# VCU_Schematic.net
KiCad netlist of a schematic drawn in Altium Designer
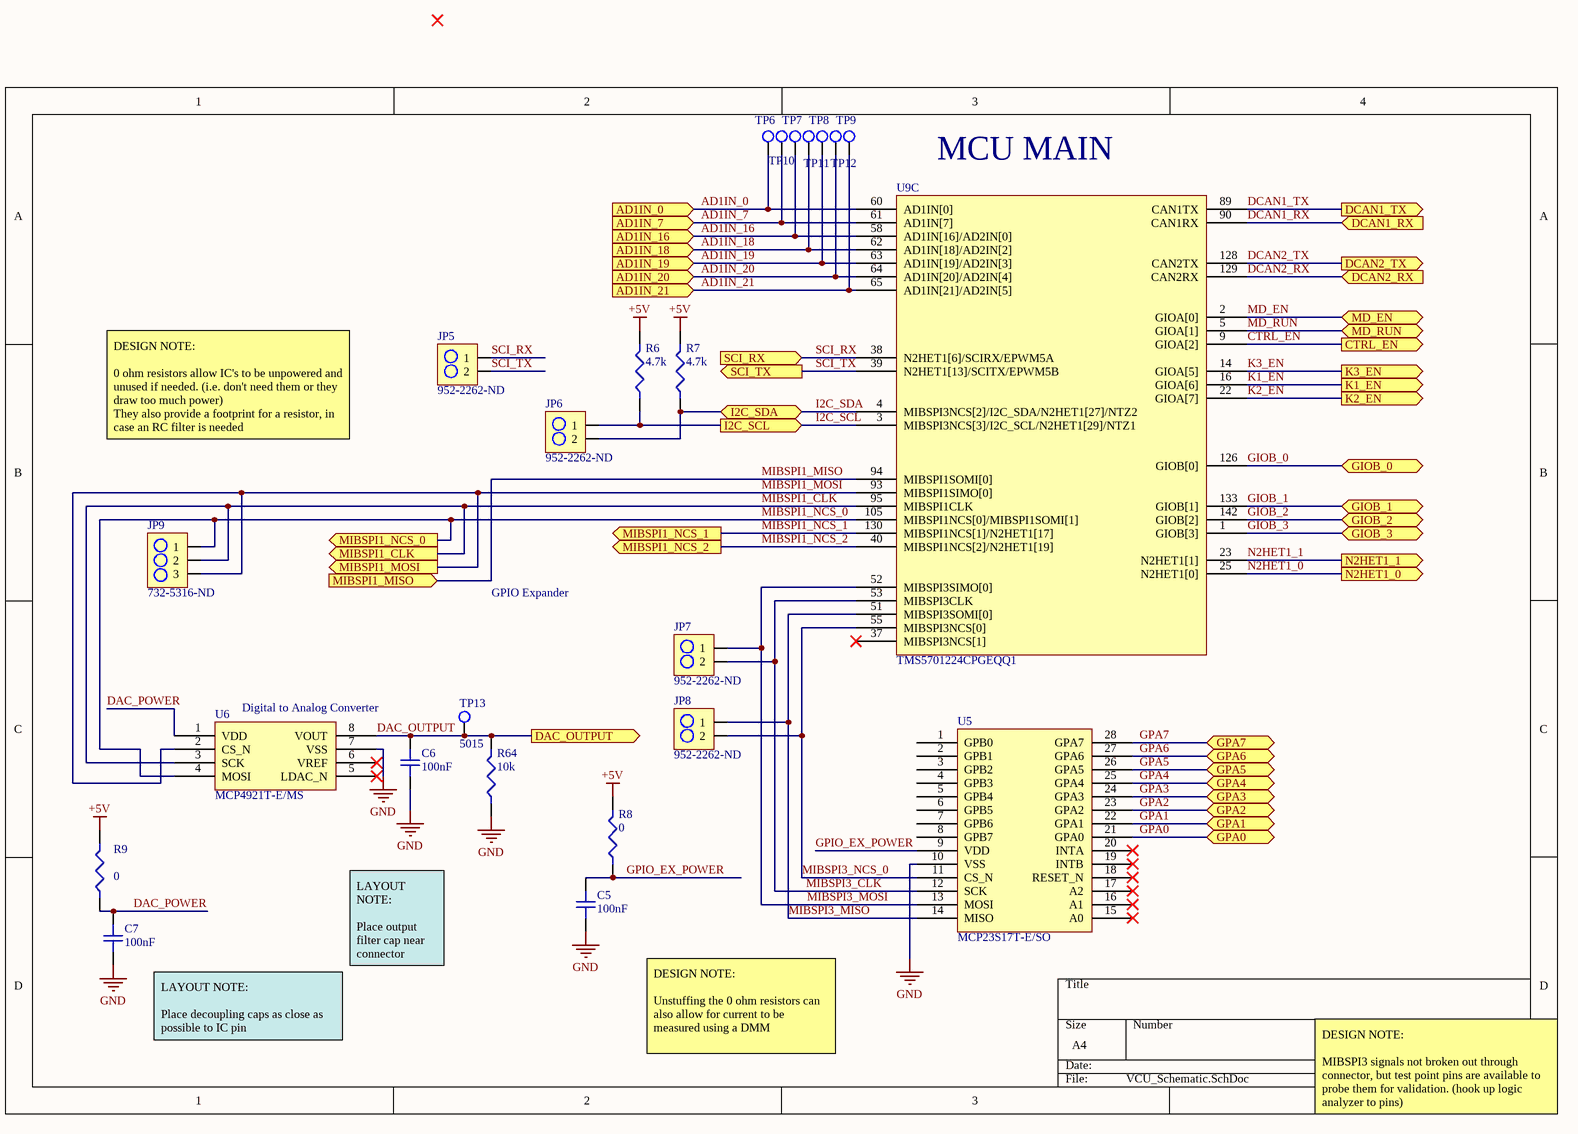
[diagram p0: VCU_Schematic.SchDoc]

(export (version "E")
  (design (tool "Eeschema 10.0.6"))
  (components
    (comp (ref "C5")
      (value "100nF")
      (footprint "PHANTOM_FOOTPRINTS:C0805")
      (description "CAP MLCC 100nF 10Volts U2J 5%")
      (fields
        (field (name "MANUFACTURER") "Murata")
        (field (name "MANUFACTURER PART NUMBER") "GRM21B7U1A104JA01L")
      )
      (libsource (lib "PHANTOM_LIBRARY") (part "GRM21B7U1A104JA01L"))
    )
    (comp (ref "C6")
      (value "100nF")
      (footprint "PHANTOM_FOOTPRINTS:C0805")
      (description "CAP MLCC 100nF 10Volts U2J 5%")
      (fields
        (field (name "MANUFACTURER") "Murata")
        (field (name "MANUFACTURER PART NUMBER") "GRM21B7U1A104JA01L")
      )
      (libsource (lib "PHANTOM_LIBRARY") (part "GRM21B7U1A104JA01L"))
    )
    (comp (ref "C7")
      (value "100nF")
      (footprint "PHANTOM_FOOTPRINTS:C0805")
      (description "CAP MLCC 100nF 10Volts U2J 5%")
      (fields
        (field (name "MANUFACTURER") "Murata")
        (field (name "MANUFACTURER PART NUMBER") "GRM21B7U1A104JA01L")
      )
      (libsource (lib "PHANTOM_LIBRARY") (part "GRM21B7U1A104JA01L"))
    )
    (comp (ref "JP5")
      (value "952-2262-ND")
      (footprint "2PIN_HEADER")
      (description "CONN_HeaderPins2pos Headers & Wire Housings 02 SIL VERTICAL PIN HEADER TIN")
      (fields (field (name "MANUFACTURER") "Harwin") (field (name "MANUFACTURER PART NUMBER") "M20-9990246"))
      (libsource (lib "PHANTOM_LIBRARY") (part "M20-9990246"))
    )
    (comp (ref "JP6")
      (value "952-2262-ND")
      (footprint "2PIN_HEADER")
      (description "CONN_HeaderPins2pos Headers & Wire Housings 02 SIL VERTICAL PIN HEADER TIN")
      (fields (field (name "MANUFACTURER") "Harwin") (field (name "MANUFACTURER PART NUMBER") "M20-9990246"))
      (libsource (lib "PHANTOM_LIBRARY") (part "M20-9990246"))
    )
    (comp (ref "JP7")
      (value "952-2262-ND")
      (footprint "2PIN_HEADER")
      (description "CONN_HeaderPins2pos Headers & Wire Housings 02 SIL VERTICAL PIN HEADER TIN")
      (fields (field (name "MANUFACTURER") "Harwin") (field (name "MANUFACTURER PART NUMBER") "M20-9990246"))
      (libsource (lib "PHANTOM_LIBRARY") (part "M20-9990246"))
    )
    (comp (ref "JP8")
      (value "952-2262-ND")
      (footprint "2PIN_HEADER")
      (description "CONN_HeaderPins2pos Headers & Wire Housings 02 SIL VERTICAL PIN HEADER TIN")
      (fields (field (name "MANUFACTURER") "Harwin") (field (name "MANUFACTURER PART NUMBER") "M20-9990246"))
      (libsource (lib "PHANTOM_LIBRARY") (part "M20-9990246"))
    )
    (comp (ref "JP9")
      (value "732-5316-ND")
      (footprint "3PIN_HEADER")
      (fields
        (field (name "MANUFACTURER") "Wurth Electronics")
        (field (name "MANUFACTURER PART NUMBER") "61300311121")
      )
      (libsource (lib "PHANTOM_LIBRARY") (part "61300311121"))
    )
    (comp (ref "R6")
      (value "4.7k")
      (footprint "R0805")
      (description "RES SMD 4.7K OHM 1% 1/8W 0805")
      (fields
        (field (name "MANUFACTURER") "Yageo")
        (field (name "MANUFACTURER PART NUMBER") "RC0805FR-074K7L")
      )
      (libsource (lib "PHANTOM_LIBRARY") (part "RC0805FR-074K7L"))
    )
    (comp (ref "R7")
      (value "4.7k")
      (footprint "R0805")
      (description "RES SMD 4.7K OHM 1% 1/8W 0805")
      (fields
        (field (name "MANUFACTURER") "Yageo")
        (field (name "MANUFACTURER PART NUMBER") "RC0805FR-074K7L")
      )
      (libsource (lib "PHANTOM_LIBRARY") (part "RC0805FR-074K7L"))
    )
    (comp (ref "R8")
      (value "0")
      (footprint "R0805")
      (description "RES SMD 0 OHM 1/8W 0805")
      (fields
        (field (name "MANUFACTURER") "Yageo")
        (field (name "MANUFACTURER PART NUMBER") "RC0805JR-070RL")
      )
      (libsource (lib "PHANTOM_LIBRARY") (part "RC0805JR-070RL"))
    )
    (comp (ref "R9")
      (value "0")
      (footprint "R0805")
      (description "RES SMD 0 OHM 1/8W 0805")
      (fields
        (field (name "MANUFACTURER") "Yageo")
        (field (name "MANUFACTURER PART NUMBER") "RC0805JR-070RL")
      )
      (libsource (lib "PHANTOM_LIBRARY") (part "RC0805JR-070RL"))
    )
    (comp (ref "R64")
      (value "10k")
      (footprint "R0805")
      (description "RES SMD 10K OHM 1% 1/8W 0805")
      (fields
        (field (name "MANUFACTURER") "Yageo Phycomp")
        (field (name "MANUFACTURER PART NUMBER") "RC0805FR-071KL")
      )
      (libsource (lib "PHANTOM_LIBRARY") (part "RC0805FR-071KL"))
    )
    (comp (ref "TP6")
      (value "5015")
      (footprint "TP_HOOK")
      (description "TEST POINT, PCB, SMT")
      (fields (field (name "MANUFACTURER") "Keystone Electronics"))
      (libsource (lib "PHANTOM_LIBRARY") (part "5015"))
    )
    (comp (ref "TP7")
      (value "5015")
      (footprint "TP_HOOK")
      (description "TEST POINT, PCB, SMT")
      (fields (field (name "MANUFACTURER") "Keystone Electronics"))
      (libsource (lib "PHANTOM_LIBRARY") (part "5015"))
    )
    (comp (ref "TP8")
      (value "5015")
      (footprint "TP_HOOK")
      (description "TEST POINT, PCB, SMT")
      (fields (field (name "MANUFACTURER") "Keystone Electronics"))
      (libsource (lib "PHANTOM_LIBRARY") (part "5015"))
    )
    (comp (ref "TP9")
      (value "5015")
      (footprint "TP_HOOK")
      (description "TEST POINT, PCB, SMT")
      (fields (field (name "MANUFACTURER") "Keystone Electronics"))
      (libsource (lib "PHANTOM_LIBRARY") (part "5015"))
    )
    (comp (ref "TP10")
      (value "5015")
      (footprint "TP_HOOK")
      (description "TEST POINT, PCB, SMT")
      (fields (field (name "MANUFACTURER") "Keystone Electronics"))
      (libsource (lib "PHANTOM_LIBRARY") (part "5015"))
    )
    (comp (ref "TP11")
      (value "5015")
      (footprint "TP_HOOK")
      (description "TEST POINT, PCB, SMT")
      (fields (field (name "MANUFACTURER") "Keystone Electronics"))
      (libsource (lib "PHANTOM_LIBRARY") (part "5015"))
    )
    (comp (ref "TP12")
      (value "5015")
      (footprint "TP_HOOK")
      (description "TEST POINT, PCB, SMT")
      (fields (field (name "MANUFACTURER") "Keystone Electronics"))
      (libsource (lib "PHANTOM_LIBRARY") (part "5015"))
    )
    (comp (ref "TP13")
      (value "5015")
      (footprint "TP_HOOK")
      (description "TEST POINT, PCB, SMT")
      (fields (field (name "MANUFACTURER") "Keystone Electronics"))
      (libsource (lib "PHANTOM_LIBRARY") (part "5015"))
    )
    (comp (ref "U5")
      (value "MCP23S17T-E/SO")
      (footprint "28-SOIC_MCP23S17")
      (description "IC I/O Expander, 16bit, 10 MHz, SPI, 4.5 V, 5.5 V, SOIC")
      (fields (field (name "MANUFACTURER") "Microchip"))
      (libsource (lib "PHANTOM_LIBRARY") (part "MCP23S17T-E/SO"))
    )
    (comp (ref "U6")
      (value "MCP4921T-E/MS")
      (footprint "8-MSOP_MCP4921")
      (description "IC Digital to Analog Converters - DAC Sgl 12-bit SPI int")
      (fields (field (name "MANUFACTURER") "Microchip"))
      (libsource (lib "PHANTOM_LIBRARY") (part "MCP4921T-E/MS"))
    )
    (comp (ref "U9")
      (value "TMS5701224CPGEQQ1")
      (footprint "LQFP-144")
      (description "ARM CORTEX R4 LOCK STEP HERCULES MCU")
      (fields (field (name "MANUFACTURER") "Texas Instruments"))
      (libsource (lib "PHANTOM_LIBRARY") (part "TMS5701224CPGEQQ1"))
    )
  )
  (nets
    (net (code "1") (name "+5V") (class "Default")
      (node (ref "R6") (pin "2") (pinfunction "2_2") (pintype "passive"))
      (node (ref "R7") (pin "2") (pinfunction "2_2") (pintype "passive"))
      (node (ref "R8") (pin "2") (pinfunction "2_2") (pintype "passive"))
      (node (ref "R9") (pin "2") (pinfunction "2_2") (pintype "passive"))
    )
    (net (code "2") (name "/AD1IN_0") (class "Default")
      (node (ref "TP6") (pin "1") (pinfunction "1_1") (pintype "passive"))
      (node (ref "U9") (pin "60") (pinfunction "AD1IN[0]_60") (pintype "passive"))
    )
    (net (code "3") (name "/AD1IN_7") (class "Default")
      (node (ref "TP10") (pin "1") (pinfunction "1_1") (pintype "passive"))
      (node (ref "U9") (pin "61") (pinfunction "AD1IN[7]_61") (pintype "passive"))
    )
    (net (code "4") (name "/AD1IN_16") (class "Default")
      (node (ref "TP7") (pin "1") (pinfunction "1_1") (pintype "passive"))
      (node (ref "U9") (pin "58") (pinfunction "AD1IN[16]/AD2IN[0]_58") (pintype "passive"))
    )
    (net (code "5") (name "/AD1IN_18") (class "Default")
      (node (ref "TP11") (pin "1") (pinfunction "1_1") (pintype "passive"))
      (node (ref "U9") (pin "62") (pinfunction "AD1IN[18]/AD2IN[2]_62") (pintype "passive"))
    )
    (net (code "6") (name "/AD1IN_19") (class "Default")
      (node (ref "TP8") (pin "1") (pinfunction "1_1") (pintype "passive"))
      (node (ref "U9") (pin "63") (pinfunction "AD1IN[19]/AD2IN[3]_63") (pintype "passive"))
    )
    (net (code "7") (name "/AD1IN_20") (class "Default")
      (node (ref "TP12") (pin "1") (pinfunction "1_1") (pintype "passive"))
      (node (ref "U9") (pin "64") (pinfunction "AD1IN[20]/AD2IN[4]_64") (pintype "passive"))
    )
    (net (code "8") (name "/AD1IN_21") (class "Default")
      (node (ref "TP9") (pin "1") (pinfunction "1_1") (pintype "passive"))
      (node (ref "U9") (pin "65") (pinfunction "AD1IN[21]/AD2IN[5]_65") (pintype "passive"))
    )
    (net (code "9") (name "/CTRL_EN") (class "Default")
      (node (ref "U9") (pin "9") (pinfunction "GIOA[2]_9") (pintype "passive"))
    )
    (net (code "10") (name "/DAC_OUTPUT") (class "Default")
      (node (ref "C6") (pin "2") (pinfunction "2_2") (pintype "passive"))
      (node (ref "R64") (pin "2") (pinfunction "2_2") (pintype "passive"))
      (node (ref "TP13") (pin "1") (pinfunction "1_1") (pintype "passive"))
      (node (ref "U6") (pin "8") (pinfunction "VOUT_8") (pintype "passive"))
    )
    (net (code "11") (name "/DAC_POWER") (class "Default")
      (node (ref "C7") (pin "2") (pinfunction "2_2") (pintype "passive"))
      (node (ref "R9") (pin "1") (pinfunction "1_1") (pintype "passive"))
      (node (ref "U6") (pin "1") (pinfunction "VDD_1") (pintype "passive"))
    )
    (net (code "12") (name "/DCAN1_RX") (class "Default")
      (node (ref "U9") (pin "90") (pinfunction "CAN1RX_90") (pintype "passive"))
    )
    (net (code "13") (name "/DCAN1_TX") (class "Default")
      (node (ref "U9") (pin "89") (pinfunction "CAN1TX_89") (pintype "passive"))
    )
    (net (code "14") (name "/DCAN2_RX") (class "Default")
      (node (ref "U9") (pin "129") (pinfunction "CAN2RX_129") (pintype "passive"))
    )
    (net (code "15") (name "/DCAN2_TX") (class "Default")
      (node (ref "U9") (pin "128") (pinfunction "CAN2TX_128") (pintype "passive"))
    )
    (net (code "16") (name "/GIOB_0") (class "Default")
      (node (ref "U9") (pin "126") (pinfunction "GIOB[0]_126") (pintype "passive"))
    )
    (net (code "17") (name "/GIOB_1") (class "Default")
      (node (ref "U9") (pin "133") (pinfunction "GIOB[1]_133") (pintype "passive"))
    )
    (net (code "18") (name "/GIOB_2") (class "Default")
      (node (ref "U9") (pin "142") (pinfunction "GIOB[2]_142") (pintype "passive"))
    )
    (net (code "19") (name "/GIOB_3") (class "Default")
      (node (ref "U9") (pin "1") (pinfunction "GIOB[3]_1") (pintype "passive"))
    )
    (net (code "20") (name "/GPA0") (class "Default")
      (node (ref "U5") (pin "21") (pinfunction "GPA0_21") (pintype "passive"))
    )
    (net (code "21") (name "/GPA1") (class "Default")
      (node (ref "U5") (pin "22") (pinfunction "GPA1_22") (pintype "passive"))
    )
    (net (code "22") (name "/GPA2") (class "Default")
      (node (ref "U5") (pin "23") (pinfunction "GPA2_23") (pintype "passive"))
    )
    (net (code "23") (name "/GPA3") (class "Default")
      (node (ref "U5") (pin "24") (pinfunction "GPA3_24") (pintype "passive"))
    )
    (net (code "24") (name "/GPA4") (class "Default")
      (node (ref "U5") (pin "25") (pinfunction "GPA4_25") (pintype "passive"))
    )
    (net (code "25") (name "/GPA5") (class "Default")
      (node (ref "U5") (pin "26") (pinfunction "GPA5_26") (pintype "passive"))
    )
    (net (code "26") (name "/GPA6") (class "Default")
      (node (ref "U5") (pin "27") (pinfunction "GPA6_27") (pintype "passive"))
    )
    (net (code "27") (name "/GPA7") (class "Default")
      (node (ref "U5") (pin "28") (pinfunction "GPA7_28") (pintype "passive"))
    )
    (net (code "28") (name "/GPIO_EX_POWER") (class "Default")
      (node (ref "C5") (pin "2") (pinfunction "2_2") (pintype "passive"))
      (node (ref "R8") (pin "1") (pinfunction "1_1") (pintype "passive"))
      (node (ref "U5") (pin "9") (pinfunction "VDD_9") (pintype "passive"))
    )
    (net (code "29") (name "/I2C_SCL") (class "Default")
      (node (ref "JP6") (pin "1") (pinfunction "1_1") (pintype "passive"))
      (node (ref "R6") (pin "1") (pinfunction "1_1") (pintype "passive"))
      (node (ref "U9") (pin "3") (pinfunction "MIBSPI3NCS[3]/I2C_SCL/N2HET1[29]/NTZ1_3") (pintype "passive"))
    )
    (net (code "30") (name "/I2C_SDA") (class "Default")
      (node (ref "JP6") (pin "2") (pinfunction "2_2") (pintype "passive"))
      (node (ref "R7") (pin "1") (pinfunction "1_1") (pintype "passive"))
      (node (ref "U9") (pin "4") (pinfunction "MIBSPI3NCS[2]/I2C_SDA/N2HET1[27]/NTZ2_4") (pintype "passive"))
    )
    (net (code "31") (name "/K1_EN") (class "Default")
      (node (ref "U9") (pin "16") (pinfunction "GIOA[6]_16") (pintype "passive"))
    )
    (net (code "32") (name "/K2_EN") (class "Default")
      (node (ref "U9") (pin "22") (pinfunction "GIOA[7]_22") (pintype "passive"))
    )
    (net (code "33") (name "/K3_EN") (class "Default")
      (node (ref "U9") (pin "14") (pinfunction "GIOA[5]_14") (pintype "passive"))
    )
    (net (code "34") (name "/MD_EN") (class "Default")
      (node (ref "U9") (pin "2") (pinfunction "GIOA[0]_2") (pintype "passive"))
    )
    (net (code "35") (name "/MD_RUN") (class "Default")
      (node (ref "U9") (pin "5") (pinfunction "GIOA[1]_5") (pintype "passive"))
    )
    (net (code "36") (name "/MIBSPI1_CLK") (class "Default")
      (node (ref "JP9") (pin "2") (pinfunction "2_2") (pintype "passive"))
      (node (ref "U6") (pin "3") (pinfunction "SCK_3") (pintype "passive"))
      (node (ref "U9") (pin "95") (pinfunction "MIBSPI1CLK_95") (pintype "passive"))
    )
    (net (code "37") (name "/MIBSPI1_MISO") (class "Default")
      (node (ref "U9") (pin "94") (pinfunction "MIBSPI1SOMI[0]_94") (pintype "passive"))
    )
    (net (code "38") (name "/MIBSPI1_MOSI") (class "Default")
      (node (ref "JP9") (pin "3") (pinfunction "3_3") (pintype "passive"))
      (node (ref "U6") (pin "2") (pinfunction "CS_N_2") (pintype "passive"))
      (node (ref "U9") (pin "93") (pinfunction "MIBSPI1SIMO[0]_93") (pintype "passive"))
    )
    (net (code "39") (name "/MIBSPI1_NCS_0") (class "Default")
      (node (ref "JP9") (pin "1") (pinfunction "1_1") (pintype "passive"))
      (node (ref "U6") (pin "4") (pinfunction "MOSI_4") (pintype "passive"))
      (node (ref "U9") (pin "105") (pinfunction "MIBSPI1NCS[0]/MIBSPI1SOMI[1]_105") (pintype "passive"))
    )
    (net (code "40") (name "/MIBSPI1_NCS_1") (class "Default")
      (node (ref "U9") (pin "130") (pinfunction "MIBSPI1NCS[1]/N2HET1[17]_130") (pintype "passive"))
    )
    (net (code "41") (name "/MIBSPI1_NCS_2") (class "Default")
      (node (ref "U9") (pin "40") (pinfunction "MIBSPI1NCS[2]/N2HET1[19]_40") (pintype "passive"))
    )
    (net (code "42") (name "/MIBSPI3_CLK") (class "Default")
      (node (ref "JP7") (pin "2") (pinfunction "2_2") (pintype "passive"))
      (node (ref "U5") (pin "12") (pinfunction "SCK_12") (pintype "passive"))
      (node (ref "U9") (pin "53") (pinfunction "MIBSPI3CLK_53") (pintype "passive"))
    )
    (net (code "43") (name "/MIBSPI3_MISO") (class "Default")
      (node (ref "JP8") (pin "1") (pinfunction "1_1") (pintype "passive"))
      (node (ref "U5") (pin "14") (pinfunction "MISO_14") (pintype "passive"))
      (node (ref "U9") (pin "51") (pinfunction "MIBSPI3SOMI[0]_51") (pintype "passive"))
    )
    (net (code "44") (name "/MIBSPI3_MOSI") (class "Default")
      (node (ref "JP7") (pin "1") (pinfunction "1_1") (pintype "passive"))
      (node (ref "U5") (pin "13") (pinfunction "MOSI_13") (pintype "passive"))
      (node (ref "U9") (pin "52") (pinfunction "MIBSPI3SIMO[0]_52") (pintype "passive"))
    )
    (net (code "45") (name "/MIBSPI3_NCS_0") (class "Default")
      (node (ref "JP8") (pin "2") (pinfunction "2_2") (pintype "passive"))
      (node (ref "U5") (pin "11") (pinfunction "CS_N_11") (pintype "passive"))
      (node (ref "U9") (pin "55") (pinfunction "MIBSPI3NCS[0]_55") (pintype "passive"))
    )
    (net (code "46") (name "/N2HET1_0") (class "Default")
      (node (ref "U9") (pin "25") (pinfunction "N2HET1[0]_25") (pintype "passive"))
    )
    (net (code "47") (name "/N2HET1_1") (class "Default")
      (node (ref "U9") (pin "23") (pinfunction "N2HET1[1]_23") (pintype "passive"))
    )
    (net (code "48") (name "/SCI_RX") (class "Default")
      (node (ref "JP5") (pin "1") (pinfunction "1_1") (pintype "passive"))
      (node (ref "U9") (pin "38") (pinfunction "N2HET1[6]/SCIRX/EPWM5A_38") (pintype "passive"))
    )
    (net (code "49") (name "/SCI_TX") (class "Default")
      (node (ref "JP5") (pin "2") (pinfunction "2_2") (pintype "passive"))
      (node (ref "U9") (pin "39") (pinfunction "N2HET1[13]/SCITX/EPWM5B_39") (pintype "passive"))
    )
    (net (code "50") (name "GND") (class "Default")
      (node (ref "C5") (pin "1") (pinfunction "1_1") (pintype "passive"))
      (node (ref "C6") (pin "1") (pinfunction "1_1") (pintype "passive"))
      (node (ref "C7") (pin "1") (pinfunction "1_1") (pintype "passive"))
      (node (ref "R64") (pin "1") (pinfunction "1_1") (pintype "passive"))
      (node (ref "U5") (pin "10") (pinfunction "VSS_10") (pintype "passive"))
      (node (ref "U6") (pin "7") (pinfunction "VSS_7") (pintype "passive"))
    )
    (net (code "51") (name "unconnected-(U5-A0-Pad15)") (class "Default")
      (node (ref "U5") (pin "15") (pinfunction "A0_15") (pintype "passive+no_connect"))
    )
    (net (code "52") (name "unconnected-(U5-A1-Pad16)") (class "Default")
      (node (ref "U5") (pin "16") (pinfunction "A1_16") (pintype "passive+no_connect"))
    )
    (net (code "53") (name "unconnected-(U5-A2-Pad17)") (class "Default")
      (node (ref "U5") (pin "17") (pinfunction "A2_17") (pintype "passive+no_connect"))
    )
    (net (code "54") (name "unconnected-(U5-GPB0-Pad1)") (class "Default")
      (node (ref "U5") (pin "1") (pinfunction "GPB0_1") (pintype "passive"))
    )
    (net (code "55") (name "unconnected-(U5-GPB1-Pad2)") (class "Default")
      (node (ref "U5") (pin "2") (pinfunction "GPB1_2") (pintype "passive"))
    )
    (net (code "56") (name "unconnected-(U5-GPB2-Pad3)") (class "Default")
      (node (ref "U5") (pin "3") (pinfunction "GPB2_3") (pintype "passive"))
    )
    (net (code "57") (name "unconnected-(U5-GPB3-Pad4)") (class "Default")
      (node (ref "U5") (pin "4") (pinfunction "GPB3_4") (pintype "passive"))
    )
    (net (code "58") (name "unconnected-(U5-GPB4-Pad5)") (class "Default")
      (node (ref "U5") (pin "5") (pinfunction "GPB4_5") (pintype "passive"))
    )
    (net (code "59") (name "unconnected-(U5-GPB5-Pad6)") (class "Default")
      (node (ref "U5") (pin "6") (pinfunction "GPB5_6") (pintype "passive"))
    )
    (net (code "60") (name "unconnected-(U5-GPB6-Pad7)") (class "Default")
      (node (ref "U5") (pin "7") (pinfunction "GPB6_7") (pintype "passive"))
    )
    (net (code "61") (name "unconnected-(U5-GPB7-Pad8)") (class "Default")
      (node (ref "U5") (pin "8") (pinfunction "GPB7_8") (pintype "passive"))
    )
    (net (code "62") (name "unconnected-(U5-INTA-Pad20)") (class "Default")
      (node (ref "U5") (pin "20") (pinfunction "INTA_20") (pintype "passive+no_connect"))
    )
    (net (code "63") (name "unconnected-(U5-INTB-Pad19)") (class "Default")
      (node (ref "U5") (pin "19") (pinfunction "INTB_19") (pintype "passive+no_connect"))
    )
    (net (code "64") (name "unconnected-(U5-RESET_N-Pad18)") (class "Default")
      (node (ref "U5") (pin "18") (pinfunction "RESET_N_18") (pintype "passive+no_connect"))
    )
    (net (code "65") (name "unconnected-(U6-LDAC_N-Pad5)") (class "Default")
      (node (ref "U6") (pin "5") (pinfunction "LDAC_N_5") (pintype "passive+no_connect"))
    )
    (net (code "66") (name "unconnected-(U6-VREF-Pad6)") (class "Default")
      (node (ref "U6") (pin "6") (pinfunction "VREF_6") (pintype "passive+no_connect"))
    )
    (net (code "67") (name "unconnected-(U9C-MIBSPI3NCS[1]-Pad37)") (class "Default")
      (node (ref "U9") (pin "37") (pinfunction "MIBSPI3NCS[1]_37") (pintype "passive+no_connect"))
    )
  )
)
